# power2.net
KiCad netlist of a schematic drawn in Altium Designer
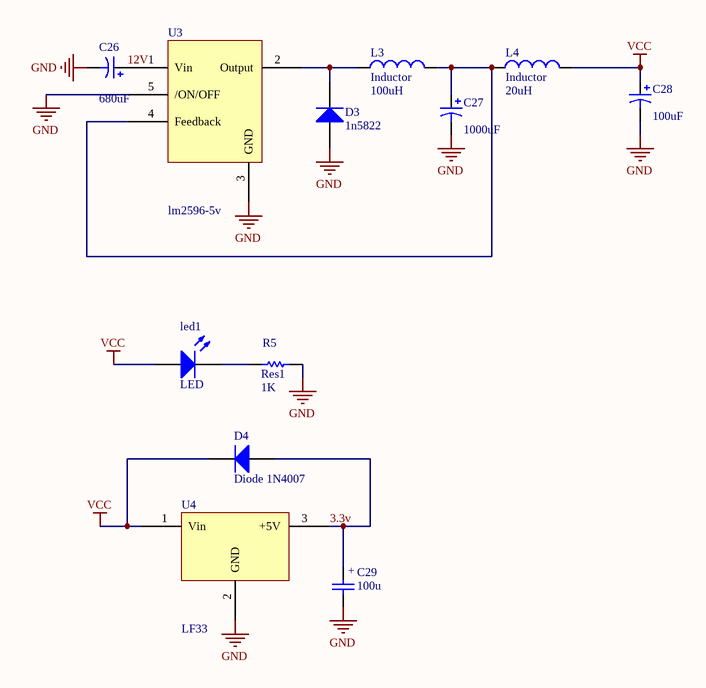
[diagram p0: power2.SchDoc]

(export (version "E")
  (design (tool "Eeschema 10.0.6"))
  (components
    (comp (ref "C26")
      (value "680uF")
      (footprint "CAP ALUM 10.3MM")
      (description "Polarized Capacitor (Radial)")
      (fields (field (name "PUBLISHER") "Altium Limited"))
      (libsource (lib "Miscellaneous Devices") (part "Cap Pol1"))
    )
    (comp (ref "C27")
      (value "1000uF")
      (footprint "CAP ALUM 10.3MM")
      (description "Polarized Capacitor (Radial)")
      (fields (field (name "PUBLISHER") "Altium Limited"))
      (libsource (lib "Miscellaneous Devices") (part "Cap Pol1"))
    )
    (comp (ref "C28")
      (value "100uF")
      (footprint "CAP ALUM 6.6MM")
      (description "Polarized Capacitor (Radial)")
      (fields (field (name "PUBLISHER") "Altium Limited"))
      (libsource (lib "Miscellaneous Devices") (part "Cap Pol1"))
    )
    (comp (ref "C29")
      (value "100u")
      (footprint "CAP ALUM 6.6MM")
      (description "CAP-3300Uf")
      (fields (field (name "Comment") "Cap"))
      (libsource (lib "Altium library (www.AVRelec.com)") (part "Cap Pol"))
    )
    (comp (ref "D3")
      (value "1n5822")
      (footprint "DO214AC SMA")
      (description "1 Amp General Purpose Rectifier")
      (fields (field (name "PUBLISHER") "Altium Limited"))
      (libsource (lib "Miscellaneous Devices") (part "Diode 1N4007"))
    )
    (comp (ref "D4")
      (value "Diode 1N4007")
      (footprint "DO214AC SMA")
      (description "1 Amp General Purpose Rectifier")
      (fields (field (name "PUBLISHER") "Altium Limited"))
      (libsource (lib "Miscellaneous Devices") (part "Diode 1N4007"))
    )
    (comp (ref "L3")
      (value "Inductor")
      (footprint "inductor - 12x12x7")
      (fields (field (name "ALTIUM_VALUE") "100uH") (field (name "PUBLISHER") "Altium Limited"))
      (libsource (lib "Miscellaneous Devices") (part "Inductor"))
    )
    (comp (ref "L4")
      (value "Inductor")
      (footprint "inductor - 12x12x7")
      (fields (field (name "ALTIUM_VALUE") "20uH") (field (name "PUBLISHER") "Altium Limited"))
      (libsource (lib "Miscellaneous Devices") (part "Inductor"))
    )
    (comp (ref "led1")
      (value "LED")
      (footprint "LED 1206/3216 RED")
      (description "Typical INFRARED GaAs LED")
      (fields (field (name "PUBLISHER") "Altium Limited"))
      (libsource (lib "Altium library (www.AVRelec.com)") (part "LED"))
    )
    (comp (ref "R5")
      (value "Res1")
      (footprint "RES 1206/3216")
      (description "Resistor")
      (fields (field (name "ALTIUM_VALUE") "1K") (field (name "PUBLISHER") "Altium Limited"))
      (libsource (lib "Miscellaneous Devices") (part "Res1"))
    )
    (comp (ref "U3")
      (value "lm2596-5v")
      (footprint "DPAK170P1430X238-6N")
      (libsource (lib "No.2") (part "lm2596"))
    )
    (comp (ref "U4")
      (value "LF33")
      (footprint "REG-7805-WALL")
      (description "Regulator")
      (libsource (lib "Altium library (www.AVRelec.com)") (part "7805"))
    )
  )
  (nets
    (net (code "1") (name "/3.3v") (class "Default")
      (node (ref "C29") (pin "+") (pinfunction "+_+") (pintype "passive"))
      (node (ref "D4") (pin "1") (pinfunction "A_1") (pintype "passive"))
      (node (ref "U4") (pin "3") (pinfunction "+5V_3") (pintype "power_in"))
    )
    (net (code "2") (name "/12V") (class "Default")
      (node (ref "C26") (pin "1") (pinfunction "1_1") (pintype "passive"))
      (node (ref "U3") (pin "1") (pinfunction "Vin_1") (pintype "power_in"))
    )
    (net (code "3") (name "GND") (class "Default")
      (node (ref "C26") (pin "2") (pinfunction "2_2") (pintype "passive"))
      (node (ref "C27") (pin "2") (pinfunction "2_2") (pintype "passive"))
      (node (ref "C28") (pin "2") (pinfunction "2_2") (pintype "passive"))
      (node (ref "C29") (pin "-") (pinfunction "-_-") (pintype "passive"))
      (node (ref "D3") (pin "1") (pinfunction "A_1") (pintype "passive"))
      (node (ref "R5") (pin "2") (pinfunction "2_2") (pintype "passive"))
      (node (ref "U3") (pin "3") (pinfunction "GND_3") (pintype "power_in"))
      (node (ref "U3") (pin "5") (pinfunction "/ON/OFF_5") (pintype "power_in"))
      (node (ref "U4") (pin "2") (pinfunction "GND_2") (pintype "power_in"))
    )
    (net (code "4") (name "Net-(D3-K)") (class "Default")
      (node (ref "D3") (pin "2") (pinfunction "K_2") (pintype "passive"))
      (node (ref "L3") (pin "1") (pinfunction "1_1") (pintype "passive"))
      (node (ref "U3") (pin "2") (pinfunction "Output_2") (pintype "power_in"))
    )
    (net (code "5") (name "Net-(R5-Pad1)") (class "Default")
      (node (ref "R5") (pin "1") (pinfunction "1_1") (pintype "passive"))
      (node (ref "led1") (pin "K") (pinfunction "K_K") (pintype "passive"))
    )
    (net (code "6") (name "Net-(U3-Feedback)") (class "Default")
      (node (ref "C27") (pin "1") (pinfunction "1_1") (pintype "passive"))
      (node (ref "L3") (pin "2") (pinfunction "2_2") (pintype "passive"))
      (node (ref "L4") (pin "1") (pinfunction "1_1") (pintype "passive"))
      (node (ref "U3") (pin "4") (pinfunction "Feedback_4") (pintype "power_in"))
    )
    (net (code "7") (name "VCC") (class "Default")
      (node (ref "C28") (pin "1") (pinfunction "1_1") (pintype "passive"))
      (node (ref "D4") (pin "2") (pinfunction "K_2") (pintype "passive"))
      (node (ref "L4") (pin "2") (pinfunction "2_2") (pintype "passive"))
      (node (ref "U4") (pin "1") (pinfunction "Vin_1") (pintype "power_in"))
      (node (ref "led1") (pin "A") (pinfunction "A_A") (pintype "passive"))
    )
  )
)
